# modules_board.net
KiCad netlist of a schematic drawn in EAGLE
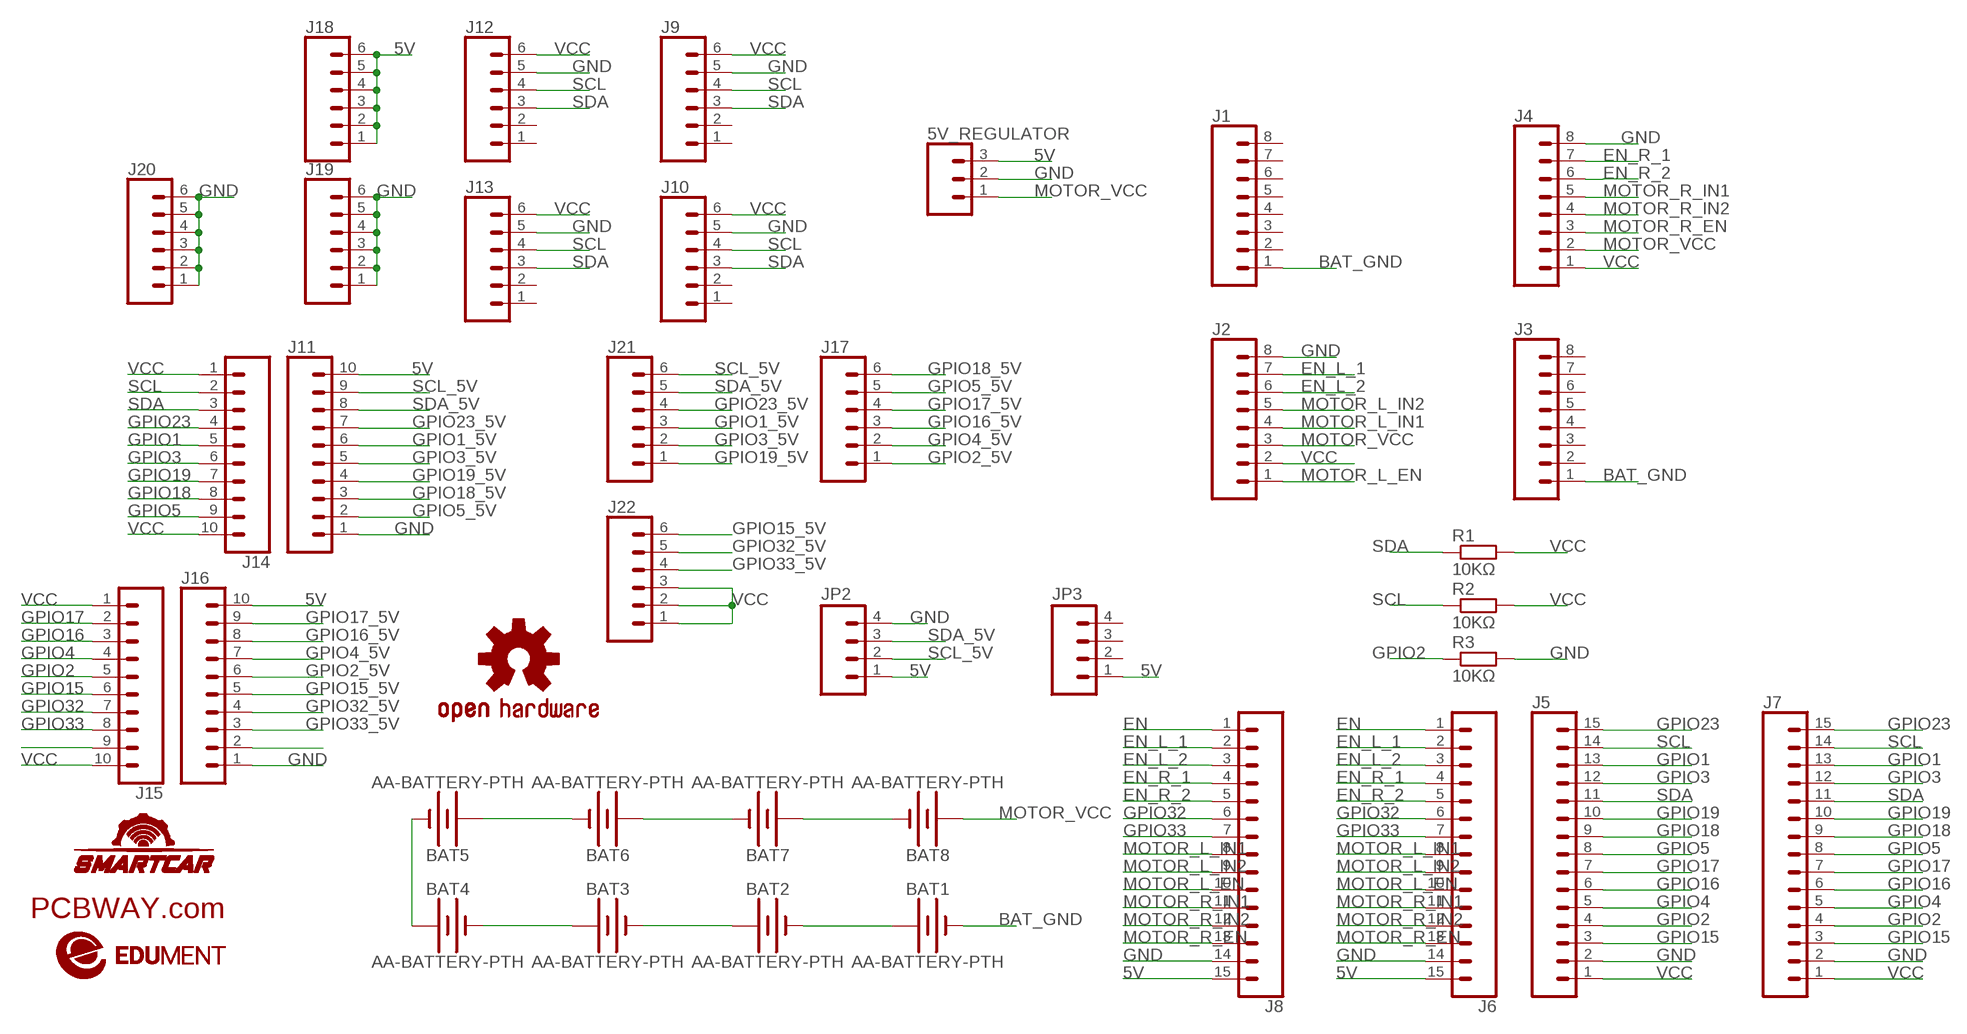
[diagram p0: schematic, sheet 1]

(export (version "E")
  (design (tool "Eeschema 10.0.6"))
  (components
    (comp (ref "5V_REGULATOR")
      (value "CONN_03LOCK")
      (footprint "eagle-import:1X03_LOCK")
      (libsource (lib "eagle-import") (part "CONN_03LOCK"))
    )
    (comp (ref "BAT1")
      (value "AA-BATTERY-PTH")
      (footprint "eagle-import:AA-PCB-BATTERY")
      (libsource (lib "eagle-import") (part "AA-BATTERY-PTH"))
    )
    (comp (ref "BAT2")
      (value "AA-BATTERY-PTH")
      (footprint "eagle-import:AA-PCB-BATTERY")
      (libsource (lib "eagle-import") (part "AA-BATTERY-PTH"))
    )
    (comp (ref "BAT3")
      (value "AA-BATTERY-PTH")
      (footprint "eagle-import:AA-PCB-BATTERY")
      (libsource (lib "eagle-import") (part "AA-BATTERY-PTH"))
    )
    (comp (ref "BAT4")
      (value "AA-BATTERY-PTH")
      (footprint "eagle-import:AA-PCB-BATTERY")
      (libsource (lib "eagle-import") (part "AA-BATTERY-PTH"))
    )
    (comp (ref "BAT5")
      (value "AA-BATTERY-PTH")
      (footprint "eagle-import:AA-PCB-BATTERY")
      (libsource (lib "eagle-import") (part "AA-BATTERY-PTH"))
    )
    (comp (ref "BAT6")
      (value "AA-BATTERY-PTH")
      (footprint "eagle-import:AA-PCB-BATTERY")
      (libsource (lib "eagle-import") (part "AA-BATTERY-PTH"))
    )
    (comp (ref "BAT7")
      (value "AA-BATTERY-PTH")
      (footprint "eagle-import:AA-PCB-BATTERY")
      (libsource (lib "eagle-import") (part "AA-BATTERY-PTH"))
    )
    (comp (ref "BAT8")
      (value "AA-BATTERY-PTH")
      (footprint "eagle-import:AA-PCB-BATTERY")
      (libsource (lib "eagle-import") (part "AA-BATTERY-PTH"))
    )
    (comp (ref "J1")
      (value "CONN_08NO_SILK_FEMALE_PTH")
      (footprint "eagle-import:1X08_NO_SILK")
      (libsource (lib "eagle-import") (part "CONN_08NO_SILK_FEMALE_PTH"))
    )
    (comp (ref "J2")
      (value "CONN_08NO_SILK_FEMALE_PTH")
      (footprint "eagle-import:1X08_NO_SILK")
      (libsource (lib "eagle-import") (part "CONN_08NO_SILK_FEMALE_PTH"))
    )
    (comp (ref "J3")
      (value "CONN_08NO_SILK_FEMALE_PTH")
      (footprint "eagle-import:1X08_NO_SILK")
      (libsource (lib "eagle-import") (part "CONN_08NO_SILK_FEMALE_PTH"))
    )
    (comp (ref "J4")
      (value "CONN_08NO_SILK_FEMALE_PTH")
      (footprint "eagle-import:1X08_NO_SILK")
      (libsource (lib "eagle-import") (part "CONN_08NO_SILK_FEMALE_PTH"))
    )
    (comp (ref "J5")
      (value "CONN_15LOCK_LONGPADS")
      (footprint "eagle-import:1X15_LOCK_LONGPADS")
      (libsource (lib "eagle-import") (part "CONN_15LOCK_LONGPADS"))
    )
    (comp (ref "J6")
      (value "CONN_15LOCK_LONGPADS")
      (footprint "eagle-import:1X15_LOCK_LONGPADS")
      (libsource (lib "eagle-import") (part "CONN_15LOCK_LONGPADS"))
    )
    (comp (ref "J7")
      (value "CONN_15LOCK_NO_SILK")
      (footprint "eagle-import:1X15_LOCK_NO_SILK")
      (libsource (lib "eagle-import") (part "CONN_15LOCK_NO_SILK"))
    )
    (comp (ref "J8")
      (value "CONN_15LOCK_NO_SILK")
      (footprint "eagle-import:1X15_LOCK_NO_SILK")
      (libsource (lib "eagle-import") (part "CONN_15LOCK_NO_SILK"))
    )
    (comp (ref "J9")
      (value "CONN_06LOCK")
      (footprint "eagle-import:1X06_LOCK")
      (libsource (lib "eagle-import") (part "CONN_06LOCK"))
    )
    (comp (ref "J10")
      (value "CONN_06LOCK")
      (footprint "eagle-import:1X06_LOCK")
      (libsource (lib "eagle-import") (part "CONN_06LOCK"))
    )
    (comp (ref "J11")
      (value "CONN_10\"")
      (footprint "eagle-import:1X10")
      (libsource (lib "eagle-import") (part "CONN_10{dblquote}"))
    )
    (comp (ref "J12")
      (value "CONN_06LOCK")
      (footprint "eagle-import:1X06_LOCK")
      (libsource (lib "eagle-import") (part "CONN_06LOCK"))
    )
    (comp (ref "J13")
      (value "CONN_06LOCK")
      (footprint "eagle-import:1X06_LOCK")
      (libsource (lib "eagle-import") (part "CONN_06LOCK"))
    )
    (comp (ref "J14")
      (value "CONN_10\"")
      (footprint "eagle-import:1X10")
      (libsource (lib "eagle-import") (part "CONN_10{dblquote}"))
    )
    (comp (ref "J15")
      (value "CONN_10\"")
      (footprint "eagle-import:1X10")
      (libsource (lib "eagle-import") (part "CONN_10{dblquote}"))
    )
    (comp (ref "J16")
      (value "CONN_10\"")
      (footprint "eagle-import:1X10")
      (libsource (lib "eagle-import") (part "CONN_10{dblquote}"))
    )
    (comp (ref "J17")
      (value "CONN_06LOCK")
      (footprint "eagle-import:1X06_LOCK")
      (libsource (lib "eagle-import") (part "CONN_06LOCK"))
    )
    (comp (ref "J18")
      (value "CONN_06LOCK")
      (footprint "eagle-import:1X06_LOCK")
      (libsource (lib "eagle-import") (part "CONN_06LOCK"))
    )
    (comp (ref "J19")
      (value "CONN_06LOCK")
      (footprint "eagle-import:1X06_LOCK")
      (libsource (lib "eagle-import") (part "CONN_06LOCK"))
    )
    (comp (ref "J20")
      (value "CONN_06LOCK")
      (footprint "eagle-import:1X06_LOCK")
      (libsource (lib "eagle-import") (part "CONN_06LOCK"))
    )
    (comp (ref "J21")
      (value "CONN_06LOCK")
      (footprint "eagle-import:1X06_LOCK")
      (libsource (lib "eagle-import") (part "CONN_06LOCK"))
    )
    (comp (ref "J22")
      (value "CONN_06LOCK")
      (footprint "eagle-import:1X06_LOCK")
      (libsource (lib "eagle-import") (part "CONN_06LOCK"))
    )
    (comp (ref "JP2")
      (value "M04NO_SILK_ALL_ROUND")
      (footprint "eagle-import:1X04_NO_SILK_ALL_ROUND")
      (libsource (lib "eagle-import") (part "M04NO_SILK_ALL_ROUND"))
    )
    (comp (ref "JP3")
      (value "M04NO_SILK_ALL_ROUND")
      (footprint "eagle-import:1X04_NO_SILK_ALL_ROUND")
      (libsource (lib "eagle-import") (part "M04NO_SILK_ALL_ROUND"))
    )
    (comp (ref "LOGO1")
      (value "OSHW-LOGOL")
      (footprint "eagle-import:OSHW-LOGO-L")
      (libsource (lib "eagle-import") (part "OSHW-LOGOL"))
    )
    (comp (ref "R1")
      (value "10KΩ")
      (footprint "eagle-import:0207_12")
      (libsource (lib "eagle-import") (part "R-EU_0207/12"))
    )
    (comp (ref "R2")
      (value "10KΩ")
      (footprint "eagle-import:0207_12")
      (libsource (lib "eagle-import") (part "R-EU_0207/12"))
    )
    (comp (ref "R3")
      (value "10KΩ")
      (footprint "eagle-import:0207_12")
      (libsource (lib "eagle-import") (part "R-EU_0207/12"))
    )
    (comp (ref "SMRTCR1")
      (value "SMARTCAR_LOGOMEDIUM")
      (footprint "eagle-import:SMARTCAR_LOGO_MEDIUM")
      (libsource (lib "eagle-import") (part "SMARTCAR_LOGOMEDIUM"))
    )
    (comp (ref "U$1")
      (value "PCBWAY_LOGO")
      (footprint "eagle-import:PCBWAY_LOGO")
      (libsource (lib "eagle-import") (part "PCBWAY_LOGO"))
    )
    (comp (ref "U$2")
      (value "EDUMENT_LOGOLARGE")
      (footprint "eagle-import:EDUMENT_LOGO_LARGE")
      (libsource (lib "eagle-import") (part "EDUMENT_LOGOLARGE"))
    )
  )
  (nets
    (net (code "1") (name "/5V") (class "Default")
      (node (ref "5V_REGULATOR") (pin "3") (pinfunction "3_3") (pintype "passive"))
      (node (ref "J11") (pin "10") (pinfunction "10_10") (pintype "passive"))
      (node (ref "J16") (pin "10") (pinfunction "10_10") (pintype "passive"))
      (node (ref "J18") (pin "1") (pinfunction "1_1") (pintype "passive"))
      (node (ref "J18") (pin "2") (pinfunction "2_2") (pintype "passive"))
      (node (ref "J18") (pin "3") (pinfunction "3_3") (pintype "passive"))
      (node (ref "J18") (pin "4") (pinfunction "4_4") (pintype "passive"))
      (node (ref "J18") (pin "5") (pinfunction "5_5") (pintype "passive"))
      (node (ref "J18") (pin "6") (pinfunction "6_6") (pintype "passive"))
      (node (ref "J6") (pin "15") (pinfunction "15_15") (pintype "passive"))
      (node (ref "J8") (pin "15") (pinfunction "15_15") (pintype "passive"))
      (node (ref "JP2") (pin "1") (pinfunction "1_1") (pintype "passive"))
      (node (ref "JP3") (pin "1") (pinfunction "1_1") (pintype "passive"))
    )
    (net (code "2") (name "/BAT_GND") (class "Default")
      (node (ref "BAT1") (pin "NEG") (pinfunction "-_NEG") (pintype "power_in"))
      (node (ref "J1") (pin "1") (pinfunction "1_1") (pintype "passive"))
      (node (ref "J3") (pin "1") (pinfunction "1_1") (pintype "passive"))
    )
    (net (code "3") (name "/EN") (class "Default")
      (node (ref "J6") (pin "1") (pinfunction "1_1") (pintype "passive"))
      (node (ref "J8") (pin "1") (pinfunction "1_1") (pintype "passive"))
    )
    (net (code "4") (name "/EN_L_1") (class "Default")
      (node (ref "J2") (pin "7") (pinfunction "7_7") (pintype "passive"))
      (node (ref "J6") (pin "2") (pinfunction "2_2") (pintype "passive"))
      (node (ref "J8") (pin "2") (pinfunction "2_2") (pintype "passive"))
    )
    (net (code "5") (name "/EN_L_2") (class "Default")
      (node (ref "J2") (pin "6") (pinfunction "6_6") (pintype "passive"))
      (node (ref "J6") (pin "3") (pinfunction "3_3") (pintype "passive"))
      (node (ref "J8") (pin "3") (pinfunction "3_3") (pintype "passive"))
    )
    (net (code "6") (name "/EN_R_1") (class "Default")
      (node (ref "J4") (pin "7") (pinfunction "7_7") (pintype "passive"))
      (node (ref "J6") (pin "4") (pinfunction "4_4") (pintype "passive"))
      (node (ref "J8") (pin "4") (pinfunction "4_4") (pintype "passive"))
    )
    (net (code "7") (name "/EN_R_2") (class "Default")
      (node (ref "J4") (pin "6") (pinfunction "6_6") (pintype "passive"))
      (node (ref "J6") (pin "5") (pinfunction "5_5") (pintype "passive"))
      (node (ref "J8") (pin "5") (pinfunction "5_5") (pintype "passive"))
    )
    (net (code "8") (name "/GND") (class "Default")
      (node (ref "5V_REGULATOR") (pin "2") (pinfunction "2_2") (pintype "passive"))
      (node (ref "J10") (pin "5") (pinfunction "5_5") (pintype "passive"))
      (node (ref "J11") (pin "1") (pinfunction "1_1") (pintype "passive"))
      (node (ref "J12") (pin "5") (pinfunction "5_5") (pintype "passive"))
      (node (ref "J13") (pin "5") (pinfunction "5_5") (pintype "passive"))
      (node (ref "J16") (pin "1") (pinfunction "1_1") (pintype "passive"))
      (node (ref "J19") (pin "1") (pinfunction "1_1") (pintype "passive"))
      (node (ref "J19") (pin "2") (pinfunction "2_2") (pintype "passive"))
      (node (ref "J19") (pin "3") (pinfunction "3_3") (pintype "passive"))
      (node (ref "J19") (pin "4") (pinfunction "4_4") (pintype "passive"))
      (node (ref "J19") (pin "5") (pinfunction "5_5") (pintype "passive"))
      (node (ref "J19") (pin "6") (pinfunction "6_6") (pintype "passive"))
      (node (ref "J2") (pin "8") (pinfunction "8_8") (pintype "passive"))
      (node (ref "J20") (pin "1") (pinfunction "1_1") (pintype "passive"))
      (node (ref "J20") (pin "2") (pinfunction "2_2") (pintype "passive"))
      (node (ref "J20") (pin "3") (pinfunction "3_3") (pintype "passive"))
      (node (ref "J20") (pin "4") (pinfunction "4_4") (pintype "passive"))
      (node (ref "J20") (pin "5") (pinfunction "5_5") (pintype "passive"))
      (node (ref "J20") (pin "6") (pinfunction "6_6") (pintype "passive"))
      (node (ref "J4") (pin "8") (pinfunction "8_8") (pintype "passive"))
      (node (ref "J5") (pin "2") (pinfunction "2_2") (pintype "passive"))
      (node (ref "J6") (pin "14") (pinfunction "14_14") (pintype "passive"))
      (node (ref "J7") (pin "2") (pinfunction "2_2") (pintype "passive"))
      (node (ref "J8") (pin "14") (pinfunction "14_14") (pintype "passive"))
      (node (ref "J9") (pin "5") (pinfunction "5_5") (pintype "passive"))
      (node (ref "JP2") (pin "4") (pinfunction "4_4") (pintype "passive"))
      (node (ref "R3") (pin "2") (pinfunction "2_2") (pintype "passive"))
    )
    (net (code "9") (name "/GPIO1") (class "Default")
      (node (ref "J14") (pin "5") (pinfunction "5_5") (pintype "passive"))
      (node (ref "J5") (pin "13") (pinfunction "13_13") (pintype "passive"))
      (node (ref "J7") (pin "13") (pinfunction "13_13") (pintype "passive"))
    )
    (net (code "10") (name "/GPIO1_5V") (class "Default")
      (node (ref "J11") (pin "6") (pinfunction "6_6") (pintype "passive"))
      (node (ref "J21") (pin "3") (pinfunction "3_3") (pintype "passive"))
    )
    (net (code "11") (name "/GPIO2") (class "Default")
      (node (ref "J15") (pin "5") (pinfunction "5_5") (pintype "passive"))
      (node (ref "J5") (pin "4") (pinfunction "4_4") (pintype "passive"))
      (node (ref "J7") (pin "4") (pinfunction "4_4") (pintype "passive"))
      (node (ref "R3") (pin "1") (pinfunction "1_1") (pintype "passive"))
    )
    (net (code "12") (name "/GPIO2_5V") (class "Default")
      (node (ref "J16") (pin "6") (pinfunction "6_6") (pintype "passive"))
      (node (ref "J17") (pin "1") (pinfunction "1_1") (pintype "passive"))
    )
    (net (code "13") (name "/GPIO3") (class "Default")
      (node (ref "J14") (pin "6") (pinfunction "6_6") (pintype "passive"))
      (node (ref "J5") (pin "12") (pinfunction "12_12") (pintype "passive"))
      (node (ref "J7") (pin "12") (pinfunction "12_12") (pintype "passive"))
    )
    (net (code "14") (name "/GPIO3_5V") (class "Default")
      (node (ref "J11") (pin "5") (pinfunction "5_5") (pintype "passive"))
      (node (ref "J21") (pin "2") (pinfunction "2_2") (pintype "passive"))
    )
    (net (code "15") (name "/GPIO4") (class "Default")
      (node (ref "J15") (pin "4") (pinfunction "4_4") (pintype "passive"))
      (node (ref "J5") (pin "5") (pinfunction "5_5") (pintype "passive"))
      (node (ref "J7") (pin "5") (pinfunction "5_5") (pintype "passive"))
    )
    (net (code "16") (name "/GPIO4_5V") (class "Default")
      (node (ref "J16") (pin "7") (pinfunction "7_7") (pintype "passive"))
      (node (ref "J17") (pin "2") (pinfunction "2_2") (pintype "passive"))
    )
    (net (code "17") (name "/GPIO5") (class "Default")
      (node (ref "J14") (pin "9") (pinfunction "9_9") (pintype "passive"))
      (node (ref "J5") (pin "8") (pinfunction "8_8") (pintype "passive"))
      (node (ref "J7") (pin "8") (pinfunction "8_8") (pintype "passive"))
    )
    (net (code "18") (name "/GPIO5_5V") (class "Default")
      (node (ref "J11") (pin "2") (pinfunction "2_2") (pintype "passive"))
      (node (ref "J17") (pin "5") (pinfunction "5_5") (pintype "passive"))
    )
    (net (code "19") (name "/GPIO15") (class "Default")
      (node (ref "J15") (pin "6") (pinfunction "6_6") (pintype "passive"))
      (node (ref "J5") (pin "3") (pinfunction "3_3") (pintype "passive"))
      (node (ref "J7") (pin "3") (pinfunction "3_3") (pintype "passive"))
    )
    (net (code "20") (name "/GPIO15_5V") (class "Default")
      (node (ref "J16") (pin "5") (pinfunction "5_5") (pintype "passive"))
      (node (ref "J22") (pin "6") (pinfunction "6_6") (pintype "passive"))
    )
    (net (code "21") (name "/GPIO16") (class "Default")
      (node (ref "J15") (pin "3") (pinfunction "3_3") (pintype "passive"))
      (node (ref "J5") (pin "6") (pinfunction "6_6") (pintype "passive"))
      (node (ref "J7") (pin "6") (pinfunction "6_6") (pintype "passive"))
    )
    (net (code "22") (name "/GPIO16_5V") (class "Default")
      (node (ref "J16") (pin "8") (pinfunction "8_8") (pintype "passive"))
      (node (ref "J17") (pin "3") (pinfunction "3_3") (pintype "passive"))
    )
    (net (code "23") (name "/GPIO17") (class "Default")
      (node (ref "J15") (pin "2") (pinfunction "2_2") (pintype "passive"))
      (node (ref "J5") (pin "7") (pinfunction "7_7") (pintype "passive"))
      (node (ref "J7") (pin "7") (pinfunction "7_7") (pintype "passive"))
    )
    (net (code "24") (name "/GPIO17_5V") (class "Default")
      (node (ref "J16") (pin "9") (pinfunction "9_9") (pintype "passive"))
      (node (ref "J17") (pin "4") (pinfunction "4_4") (pintype "passive"))
    )
    (net (code "25") (name "/GPIO18") (class "Default")
      (node (ref "J14") (pin "8") (pinfunction "8_8") (pintype "passive"))
      (node (ref "J5") (pin "9") (pinfunction "9_9") (pintype "passive"))
      (node (ref "J7") (pin "9") (pinfunction "9_9") (pintype "passive"))
    )
    (net (code "26") (name "/GPIO18_5V") (class "Default")
      (node (ref "J11") (pin "3") (pinfunction "3_3") (pintype "passive"))
      (node (ref "J17") (pin "6") (pinfunction "6_6") (pintype "passive"))
    )
    (net (code "27") (name "/GPIO19") (class "Default")
      (node (ref "J14") (pin "7") (pinfunction "7_7") (pintype "passive"))
      (node (ref "J5") (pin "10") (pinfunction "10_10") (pintype "passive"))
      (node (ref "J7") (pin "10") (pinfunction "10_10") (pintype "passive"))
    )
    (net (code "28") (name "/GPIO19_5V") (class "Default")
      (node (ref "J11") (pin "4") (pinfunction "4_4") (pintype "passive"))
      (node (ref "J21") (pin "1") (pinfunction "1_1") (pintype "passive"))
    )
    (net (code "29") (name "/GPIO23") (class "Default")
      (node (ref "J14") (pin "4") (pinfunction "4_4") (pintype "passive"))
      (node (ref "J5") (pin "15") (pinfunction "15_15") (pintype "passive"))
      (node (ref "J7") (pin "15") (pinfunction "15_15") (pintype "passive"))
    )
    (net (code "30") (name "/GPIO23_5V") (class "Default")
      (node (ref "J11") (pin "7") (pinfunction "7_7") (pintype "passive"))
      (node (ref "J21") (pin "4") (pinfunction "4_4") (pintype "passive"))
    )
    (net (code "31") (name "/GPIO32") (class "Default")
      (node (ref "J15") (pin "7") (pinfunction "7_7") (pintype "passive"))
      (node (ref "J6") (pin "6") (pinfunction "6_6") (pintype "passive"))
      (node (ref "J8") (pin "6") (pinfunction "6_6") (pintype "passive"))
    )
    (net (code "32") (name "/GPIO32_5V") (class "Default")
      (node (ref "J16") (pin "4") (pinfunction "4_4") (pintype "passive"))
      (node (ref "J22") (pin "5") (pinfunction "5_5") (pintype "passive"))
    )
    (net (code "33") (name "/GPIO33") (class "Default")
      (node (ref "J15") (pin "8") (pinfunction "8_8") (pintype "passive"))
      (node (ref "J6") (pin "7") (pinfunction "7_7") (pintype "passive"))
      (node (ref "J8") (pin "7") (pinfunction "7_7") (pintype "passive"))
    )
    (net (code "34") (name "/GPIO33_5V") (class "Default")
      (node (ref "J16") (pin "3") (pinfunction "3_3") (pintype "passive"))
      (node (ref "J22") (pin "4") (pinfunction "4_4") (pintype "passive"))
    )
    (net (code "35") (name "/MOTOR_L_EN") (class "Default")
      (node (ref "J2") (pin "1") (pinfunction "1_1") (pintype "passive"))
      (node (ref "J6") (pin "10") (pinfunction "10_10") (pintype "passive"))
      (node (ref "J8") (pin "10") (pinfunction "10_10") (pintype "passive"))
    )
    (net (code "36") (name "/MOTOR_L_IN1") (class "Default")
      (node (ref "J2") (pin "4") (pinfunction "4_4") (pintype "passive"))
      (node (ref "J6") (pin "8") (pinfunction "8_8") (pintype "passive"))
      (node (ref "J8") (pin "8") (pinfunction "8_8") (pintype "passive"))
    )
    (net (code "37") (name "/MOTOR_L_IN2") (class "Default")
      (node (ref "J2") (pin "5") (pinfunction "5_5") (pintype "passive"))
      (node (ref "J6") (pin "9") (pinfunction "9_9") (pintype "passive"))
      (node (ref "J8") (pin "9") (pinfunction "9_9") (pintype "passive"))
    )
    (net (code "38") (name "/MOTOR_R_EN") (class "Default")
      (node (ref "J4") (pin "3") (pinfunction "3_3") (pintype "passive"))
      (node (ref "J6") (pin "13") (pinfunction "13_13") (pintype "passive"))
      (node (ref "J8") (pin "13") (pinfunction "13_13") (pintype "passive"))
    )
    (net (code "39") (name "/MOTOR_R_IN1") (class "Default")
      (node (ref "J4") (pin "5") (pinfunction "5_5") (pintype "passive"))
      (node (ref "J6") (pin "11") (pinfunction "11_11") (pintype "passive"))
      (node (ref "J8") (pin "11") (pinfunction "11_11") (pintype "passive"))
    )
    (net (code "40") (name "/MOTOR_R_IN2") (class "Default")
      (node (ref "J4") (pin "4") (pinfunction "4_4") (pintype "passive"))
      (node (ref "J6") (pin "12") (pinfunction "12_12") (pintype "passive"))
      (node (ref "J8") (pin "12") (pinfunction "12_12") (pintype "passive"))
    )
    (net (code "41") (name "/MOTOR_VCC") (class "Default")
      (node (ref "5V_REGULATOR") (pin "1") (pinfunction "1_1") (pintype "passive"))
      (node (ref "BAT8") (pin "POS") (pinfunction "+_POS") (pintype "power_in"))
      (node (ref "J2") (pin "3") (pinfunction "3_3") (pintype "passive"))
      (node (ref "J4") (pin "2") (pinfunction "2_2") (pintype "passive"))
    )
    (net (code "42") (name "/SCL") (class "Default")
      (node (ref "J10") (pin "4") (pinfunction "4_4") (pintype "passive"))
      (node (ref "J12") (pin "4") (pinfunction "4_4") (pintype "passive"))
      (node (ref "J13") (pin "4") (pinfunction "4_4") (pintype "passive"))
      (node (ref "J14") (pin "2") (pinfunction "2_2") (pintype "passive"))
      (node (ref "J5") (pin "14") (pinfunction "14_14") (pintype "passive"))
      (node (ref "J7") (pin "14") (pinfunction "14_14") (pintype "passive"))
      (node (ref "J9") (pin "4") (pinfunction "4_4") (pintype "passive"))
      (node (ref "R2") (pin "1") (pinfunction "1_1") (pintype "passive"))
    )
    (net (code "43") (name "/SCL_5V") (class "Default")
      (node (ref "J11") (pin "9") (pinfunction "9_9") (pintype "passive"))
      (node (ref "J21") (pin "6") (pinfunction "6_6") (pintype "passive"))
      (node (ref "JP2") (pin "2") (pinfunction "2_2") (pintype "passive"))
    )
    (net (code "44") (name "/SDA") (class "Default")
      (node (ref "J10") (pin "3") (pinfunction "3_3") (pintype "passive"))
      (node (ref "J12") (pin "3") (pinfunction "3_3") (pintype "passive"))
      (node (ref "J13") (pin "3") (pinfunction "3_3") (pintype "passive"))
      (node (ref "J14") (pin "3") (pinfunction "3_3") (pintype "passive"))
      (node (ref "J5") (pin "11") (pinfunction "11_11") (pintype "passive"))
      (node (ref "J7") (pin "11") (pinfunction "11_11") (pintype "passive"))
      (node (ref "J9") (pin "3") (pinfunction "3_3") (pintype "passive"))
      (node (ref "R1") (pin "1") (pinfunction "1_1") (pintype "passive"))
    )
    (net (code "45") (name "/SDA_5V") (class "Default")
      (node (ref "J11") (pin "8") (pinfunction "8_8") (pintype "passive"))
      (node (ref "J21") (pin "5") (pinfunction "5_5") (pintype "passive"))
      (node (ref "JP2") (pin "3") (pinfunction "3_3") (pintype "passive"))
    )
    (net (code "46") (name "/VCC") (class "Default")
      (node (ref "J10") (pin "6") (pinfunction "6_6") (pintype "passive"))
      (node (ref "J12") (pin "6") (pinfunction "6_6") (pintype "passive"))
      (node (ref "J13") (pin "6") (pinfunction "6_6") (pintype "passive"))
      (node (ref "J14") (pin "1") (pinfunction "1_1") (pintype "passive"))
      (node (ref "J14") (pin "10") (pinfunction "10_10") (pintype "passive"))
      (node (ref "J15") (pin "1") (pinfunction "1_1") (pintype "passive"))
      (node (ref "J15") (pin "10") (pinfunction "10_10") (pintype "passive"))
      (node (ref "J2") (pin "2") (pinfunction "2_2") (pintype "passive"))
      (node (ref "J22") (pin "1") (pinfunction "1_1") (pintype "passive"))
      (node (ref "J22") (pin "2") (pinfunction "2_2") (pintype "passive"))
      (node (ref "J22") (pin "3") (pinfunction "3_3") (pintype "passive"))
      (node (ref "J4") (pin "1") (pinfunction "1_1") (pintype "passive"))
      (node (ref "J5") (pin "1") (pinfunction "1_1") (pintype "passive"))
      (node (ref "J7") (pin "1") (pinfunction "1_1") (pintype "passive"))
      (node (ref "J9") (pin "6") (pinfunction "6_6") (pintype "passive"))
      (node (ref "R1") (pin "2") (pinfunction "2_2") (pintype "passive"))
      (node (ref "R2") (pin "2") (pinfunction "2_2") (pintype "passive"))
    )
    (net (code "47") (name "Net-(BAT1-+)") (class "Default")
      (node (ref "BAT1") (pin "POS") (pinfunction "+_POS") (pintype "power_in"))
      (node (ref "BAT2") (pin "NEG") (pinfunction "-_NEG") (pintype "power_in"))
    )
    (net (code "48") (name "Net-(BAT2-+)") (class "Default")
      (node (ref "BAT2") (pin "POS") (pinfunction "+_POS") (pintype "power_in"))
      (node (ref "BAT3") (pin "NEG") (pinfunction "-_NEG") (pintype "power_in"))
    )
    (net (code "49") (name "Net-(BAT3-+)") (class "Default")
      (node (ref "BAT3") (pin "POS") (pinfunction "+_POS") (pintype "power_in"))
      (node (ref "BAT4") (pin "NEG") (pinfunction "-_NEG") (pintype "power_in"))
    )
    (net (code "50") (name "Net-(BAT4-+)") (class "Default")
      (node (ref "BAT4") (pin "POS") (pinfunction "+_POS") (pintype "power_in"))
      (node (ref "BAT5") (pin "NEG") (pinfunction "-_NEG") (pintype "power_in"))
    )
    (net (code "51") (name "Net-(BAT5-+)") (class "Default")
      (node (ref "BAT5") (pin "POS") (pinfunction "+_POS") (pintype "power_in"))
      (node (ref "BAT6") (pin "NEG") (pinfunction "-_NEG") (pintype "power_in"))
    )
    (net (code "52") (name "Net-(BAT6-+)") (class "Default")
      (node (ref "BAT6") (pin "POS") (pinfunction "+_POS") (pintype "power_in"))
      (node (ref "BAT7") (pin "NEG") (pinfunction "-_NEG") (pintype "power_in"))
    )
    (net (code "53") (name "Net-(BAT7-+)") (class "Default")
      (node (ref "BAT7") (pin "POS") (pinfunction "+_POS") (pintype "power_in"))
      (node (ref "BAT8") (pin "NEG") (pinfunction "-_NEG") (pintype "power_in"))
    )
    (net (code "54") (name "unconnected-(J1-Pad2)") (class "Default")
      (node (ref "J1") (pin "2") (pinfunction "2_2") (pintype "passive"))
    )
    (net (code "55") (name "unconnected-(J1-Pad3)") (class "Default")
      (node (ref "J1") (pin "3") (pinfunction "3_3") (pintype "passive"))
    )
    (net (code "56") (name "unconnected-(J1-Pad4)") (class "Default")
      (node (ref "J1") (pin "4") (pinfunction "4_4") (pintype "passive"))
    )
    (net (code "57") (name "unconnected-(J1-Pad5)") (class "Default")
      (node (ref "J1") (pin "5") (pinfunction "5_5") (pintype "passive"))
    )
    (net (code "58") (name "unconnected-(J1-Pad6)") (class "Default")
      (node (ref "J1") (pin "6") (pinfunction "6_6") (pintype "passive"))
    )
    (net (code "59") (name "unconnected-(J1-Pad7)") (class "Default")
      (node (ref "J1") (pin "7") (pinfunction "7_7") (pintype "passive"))
    )
    (net (code "60") (name "unconnected-(J1-Pad8)") (class "Default")
      (node (ref "J1") (pin "8") (pinfunction "8_8") (pintype "passive"))
    )
    (net (code "61") (name "unconnected-(J3-Pad2)") (class "Default")
      (node (ref "J3") (pin "2") (pinfunction "2_2") (pintype "passive"))
    )
    (net (code "62") (name "unconnected-(J3-Pad3)") (class "Default")
      (node (ref "J3") (pin "3") (pinfunction "3_3") (pintype "passive"))
    )
    (net (code "63") (name "unconnected-(J3-Pad4)") (class "Default")
      (node (ref "J3") (pin "4") (pinfunction "4_4") (pintype "passive"))
    )
    (net (code "64") (name "unconnected-(J3-Pad5)") (class "Default")
      (node (ref "J3") (pin "5") (pinfunction "5_5") (pintype "passive"))
    )
    (net (code "65") (name "unconnected-(J3-Pad6)") (class "Default")
      (node (ref "J3") (pin "6") (pinfunction "6_6") (pintype "passive"))
    )
    (net (code "66") (name "unconnected-(J3-Pad7)") (class "Default")
      (node (ref "J3") (pin "7") (pinfunction "7_7") (pintype "passive"))
    )
    (net (code "67") (name "unconnected-(J3-Pad8)") (class "Default")
      (node (ref "J3") (pin "8") (pinfunction "8_8") (pintype "passive"))
    )
    (net (code "68") (name "unconnected-(J9-Pad1)") (class "Default")
      (node (ref "J9") (pin "1") (pinfunction "1_1") (pintype "passive"))
    )
    (net (code "69") (name "unconnected-(J9-Pad2)") (class "Default")
      (node (ref "J9") (pin "2") (pinfunction "2_2") (pintype "passive"))
    )
    (net (code "70") (name "unconnected-(J10-Pad1)") (class "Default")
      (node (ref "J10") (pin "1") (pinfunction "1_1") (pintype "passive"))
    )
    (net (code "71") (name "unconnected-(J10-Pad2)") (class "Default")
      (node (ref "J10") (pin "2") (pinfunction "2_2") (pintype "passive"))
    )
    (net (code "72") (name "unconnected-(J12-Pad1)") (class "Default")
      (node (ref "J12") (pin "1") (pinfunction "1_1") (pintype "passive"))
    )
    (net (code "73") (name "unconnected-(J12-Pad2)") (class "Default")
      (node (ref "J12") (pin "2") (pinfunction "2_2") (pintype "passive"))
    )
    (net (code "74") (name "unconnected-(J13-Pad1)") (class "Default")
      (node (ref "J13") (pin "1") (pinfunction "1_1") (pintype "passive"))
    )
    (net (code "75") (name "unconnected-(J13-Pad2)") (class "Default")
      (node (ref "J13") (pin "2") (pinfunction "2_2") (pintype "passive"))
    )
    (net (code "76") (name "unconnected-(J15-Pad9)") (class "Default")
      (node (ref "J15") (pin "9") (pinfunction "9_9") (pintype "passive"))
    )
    (net (code "77") (name "unconnected-(J16-Pad2)") (class "Default")
      (node (ref "J16") (pin "2") (pinfunction "2_2") (pintype "passive"))
    )
    (net (code "78") (name "unconnected-(JP3-Pad2)") (class "Default")
      (node (ref "JP3") (pin "2") (pinfunction "2_2") (pintype "passive"))
    )
    (net (code "79") (name "unconnected-(JP3-Pad3)") (class "Default")
      (node (ref "JP3") (pin "3") (pinfunction "3_3") (pintype "passive"))
    )
    (net (code "80") (name "unconnected-(JP3-Pad4)") (class "Default")
      (node (ref "JP3") (pin "4") (pinfunction "4_4") (pintype "passive"))
    )
  )
)
